# MotionDetector.net
KiCad netlist of a schematic drawn in Altium Designer
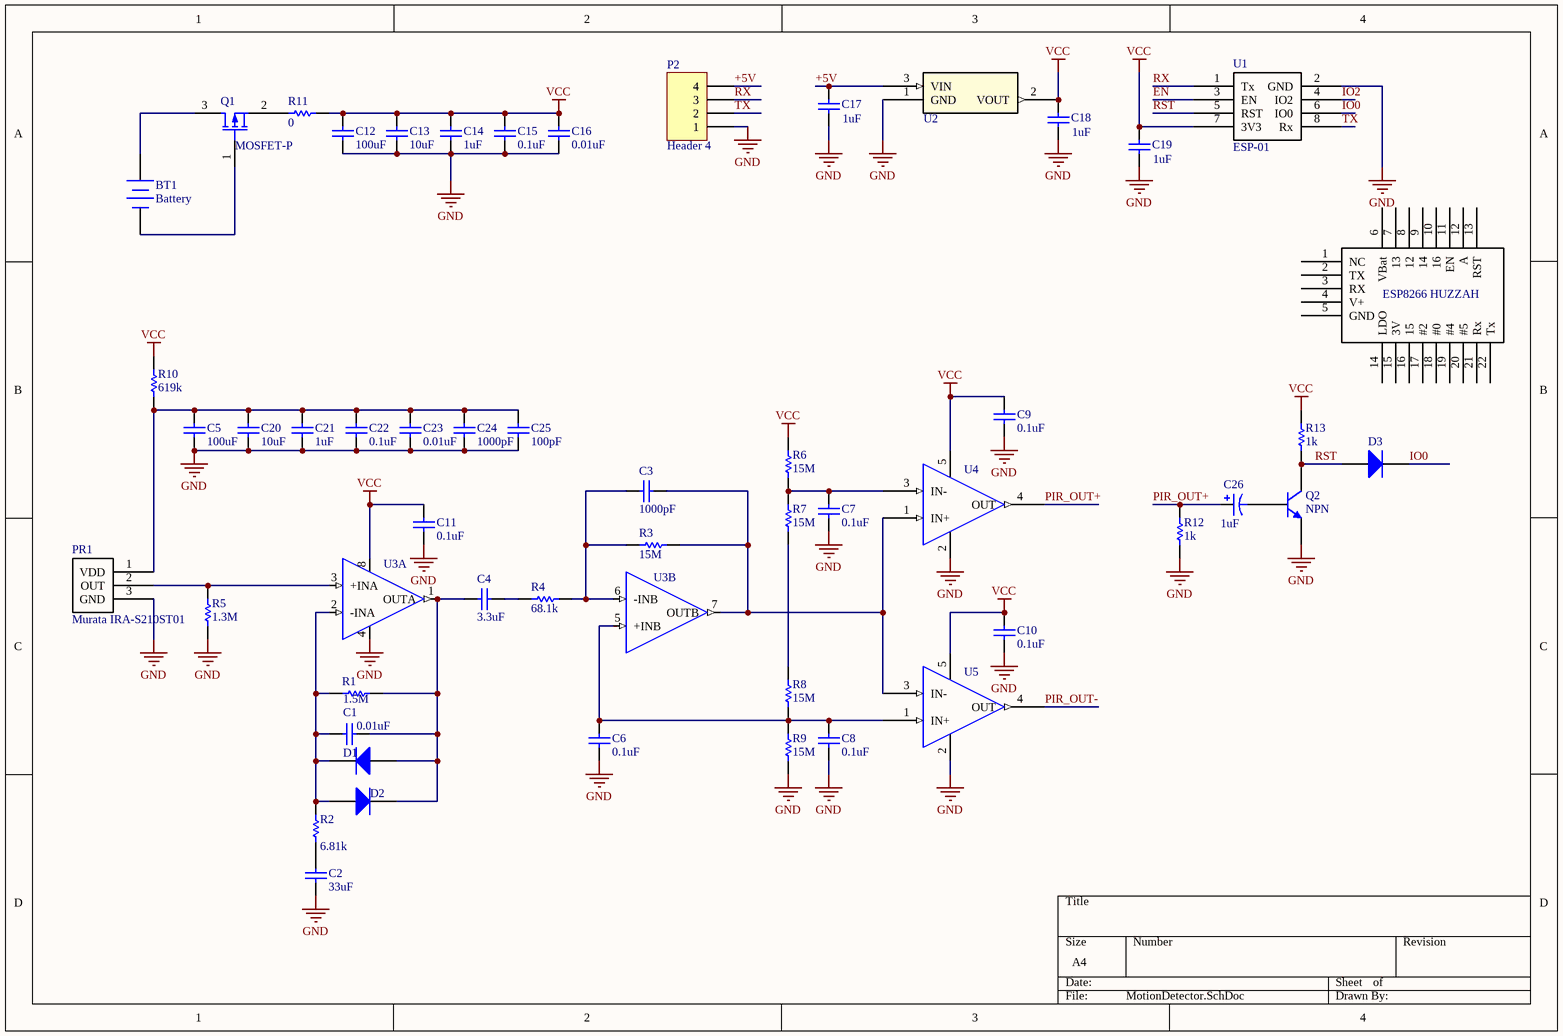
[diagram p0: MotionDetector.SchDoc]

(export (version "E")
  (design (tool "Eeschema 10.0.6"))
  (components
    (comp (ref "BT1")
      (value "Battery")
      (footprint "BAT-2")
      (description "Multicell Battery")
      (fields (field (name "PUBLISHER") "Altium Limited"))
      (libsource (lib "Miscellaneous Devices") (part "Battery"))
    )
    (comp (ref "C1")
      (value "0.01uF")
      (footprint "CAP_0804")
      (description "Capacitor")
      (fields (field (name "Comment") "Cap") (field (name "PUBLISHER") "Altium Limited"))
      (libsource (lib "Miscellaneous Devices") (part "Cap"))
    )
    (comp (ref "C2")
      (value "33uF")
      (footprint "CAP_0804")
      (description "Capacitor")
      (fields (field (name "Comment") "Cap") (field (name "PUBLISHER") "Altium Limited"))
      (libsource (lib "Miscellaneous Devices") (part "Cap"))
    )
    (comp (ref "C3")
      (value "1000pF")
      (footprint "CAP_0804")
      (description "Capacitor")
      (fields (field (name "Comment") "Cap") (field (name "PUBLISHER") "Altium Limited"))
      (libsource (lib "Miscellaneous Devices") (part "Cap"))
    )
    (comp (ref "C4")
      (value "3.3uF")
      (footprint "CAP_0804")
      (description "Capacitor")
      (fields (field (name "Comment") "Cap") (field (name "PUBLISHER") "Altium Limited"))
      (libsource (lib "Miscellaneous Devices") (part "Cap"))
    )
    (comp (ref "C5")
      (value "100uF")
      (footprint "CAP_0804")
      (description "Capacitor")
      (fields (field (name "Comment") "Cap") (field (name "PUBLISHER") "Altium Limited"))
      (libsource (lib "Miscellaneous Devices") (part "Cap"))
    )
    (comp (ref "C6")
      (value "0.1uF")
      (footprint "CAP_0804")
      (description "Capacitor")
      (fields (field (name "Comment") "Cap") (field (name "PUBLISHER") "Altium Limited"))
      (libsource (lib "Miscellaneous Devices") (part "Cap"))
    )
    (comp (ref "C7")
      (value "0.1uF")
      (footprint "CAP_0804")
      (description "Capacitor")
      (fields (field (name "Comment") "Cap") (field (name "PUBLISHER") "Altium Limited"))
      (libsource (lib "Miscellaneous Devices") (part "Cap"))
    )
    (comp (ref "C8")
      (value "0.1uF")
      (footprint "CAP_0804")
      (description "Capacitor")
      (fields (field (name "Comment") "Cap") (field (name "PUBLISHER") "Altium Limited"))
      (libsource (lib "Miscellaneous Devices") (part "Cap"))
    )
    (comp (ref "C9")
      (value "0.1uF")
      (footprint "CAP_0804")
      (description "Capacitor")
      (fields (field (name "Comment") "Cap") (field (name "PUBLISHER") "Altium Limited"))
      (libsource (lib "Miscellaneous Devices") (part "Cap"))
    )
    (comp (ref "C10")
      (value "0.1uF")
      (footprint "CAP_0804")
      (description "Capacitor")
      (fields (field (name "Comment") "Cap") (field (name "PUBLISHER") "Altium Limited"))
      (libsource (lib "Miscellaneous Devices") (part "Cap"))
    )
    (comp (ref "C11")
      (value "0.1uF")
      (footprint "CAP_0804")
      (description "Capacitor")
      (fields (field (name "Comment") "Cap") (field (name "PUBLISHER") "Altium Limited"))
      (libsource (lib "Miscellaneous Devices") (part "Cap"))
    )
    (comp (ref "C12")
      (value "100uF")
      (footprint "CAP_0804")
      (description "Capacitor")
      (fields (field (name "Comment") "Cap") (field (name "PUBLISHER") "Altium Limited"))
      (libsource (lib "Miscellaneous Devices") (part "Cap"))
    )
    (comp (ref "C13")
      (value "10uF")
      (footprint "CAP_0804")
      (description "Capacitor")
      (fields (field (name "Comment") "Cap") (field (name "PUBLISHER") "Altium Limited"))
      (libsource (lib "Miscellaneous Devices") (part "Cap"))
    )
    (comp (ref "C14")
      (value "1uF")
      (footprint "CAP_0804")
      (description "Capacitor")
      (fields (field (name "Comment") "Cap") (field (name "PUBLISHER") "Altium Limited"))
      (libsource (lib "Miscellaneous Devices") (part "Cap"))
    )
    (comp (ref "C15")
      (value "0.1uF")
      (footprint "CAP_0804")
      (description "Capacitor")
      (fields (field (name "Comment") "Cap") (field (name "PUBLISHER") "Altium Limited"))
      (libsource (lib "Miscellaneous Devices") (part "Cap"))
    )
    (comp (ref "C16")
      (value "0.01uF")
      (footprint "CAP_0804")
      (description "Capacitor")
      (fields (field (name "Comment") "Cap") (field (name "PUBLISHER") "Altium Limited"))
      (libsource (lib "Miscellaneous Devices") (part "Cap"))
    )
    (comp (ref "C17")
      (value "1uF")
      (footprint "CAP_0804")
      (description "Capacitor")
      (fields (field (name "Comment") "Cap") (field (name "PUBLISHER") "Altium Limited"))
      (libsource (lib "Miscellaneous Devices") (part "Cap"))
    )
    (comp (ref "C18")
      (value "1uF")
      (footprint "CAP_0804")
      (description "Capacitor")
      (fields (field (name "Comment") "Cap") (field (name "PUBLISHER") "Altium Limited"))
      (libsource (lib "Miscellaneous Devices") (part "Cap"))
    )
    (comp (ref "C19")
      (value "1uF")
      (footprint "CAP_0804")
      (description "Capacitor")
      (fields (field (name "Comment") "Cap") (field (name "PUBLISHER") "Altium Limited"))
      (libsource (lib "Miscellaneous Devices") (part "Cap"))
    )
    (comp (ref "C20")
      (value "10uF")
      (footprint "CAP_0804")
      (description "Capacitor")
      (fields (field (name "Comment") "Cap") (field (name "PUBLISHER") "Altium Limited"))
      (libsource (lib "Miscellaneous Devices") (part "Cap"))
    )
    (comp (ref "C21")
      (value "1uF")
      (footprint "CAP_0804")
      (description "Capacitor")
      (fields (field (name "Comment") "Cap") (field (name "PUBLISHER") "Altium Limited"))
      (libsource (lib "Miscellaneous Devices") (part "Cap"))
    )
    (comp (ref "C22")
      (value "0.1uF")
      (footprint "CAP_0804")
      (description "Capacitor")
      (fields (field (name "Comment") "Cap") (field (name "PUBLISHER") "Altium Limited"))
      (libsource (lib "Miscellaneous Devices") (part "Cap"))
    )
    (comp (ref "C23")
      (value "0.01uF")
      (footprint "CAP_0804")
      (description "Capacitor")
      (fields (field (name "Comment") "Cap") (field (name "PUBLISHER") "Altium Limited"))
      (libsource (lib "Miscellaneous Devices") (part "Cap"))
    )
    (comp (ref "C24")
      (value "1000pF")
      (footprint "CAP_0804")
      (description "Capacitor")
      (fields (field (name "Comment") "Cap") (field (name "PUBLISHER") "Altium Limited"))
      (libsource (lib "Miscellaneous Devices") (part "Cap"))
    )
    (comp (ref "C25")
      (value "100pF")
      (footprint "CAP_0804")
      (description "Capacitor")
      (fields (field (name "Comment") "Cap") (field (name "PUBLISHER") "Altium Limited"))
      (libsource (lib "Miscellaneous Devices") (part "Cap"))
    )
    (comp (ref "C26")
      (value "1uF")
      (footprint "RB7.6-15")
      (description "Polarized Capacitor (Radial)")
      (fields (field (name "Comment") "Cap Pol1") (field (name "PUBLISHER") "Altium Limited"))
      (libsource (lib "Miscellaneous Devices") (part "Cap Pol1"))
    )
    (comp (ref "D1")
      (value "Diode")
      (footprint "Diode SOD123")
      (description "Default Diode")
      (fields (field (name "PUBLISHER") "Altium Limited"))
      (libsource (lib "Miscellaneous Devices") (part "Diode"))
    )
    (comp (ref "D2")
      (value "Diode")
      (footprint "Diode SOD123")
      (description "Default Diode")
      (fields (field (name "PUBLISHER") "Altium Limited"))
      (libsource (lib "Miscellaneous Devices") (part "Diode"))
    )
    (comp (ref "D3")
      (value "Diode")
      (footprint "Diode SOD123")
      (description "Default Diode")
      (fields (field (name "PUBLISHER") "Altium Limited"))
      (libsource (lib "Miscellaneous Devices") (part "Diode"))
    )
    (comp (ref "ESP8266 HUZZAH")
      (value "Wifi module")
      (footprint "ESP8266 HUZZAH - duplicate")
      (description "U3")
      (libsource (lib "MotionDetectorSchematicLib") (part "U1"))
    )
    (comp (ref "P2")
      (value "Header 4")
      (footprint "HDR1X4")
      (description "Header, 4-Pin")
      (fields (field (name "PUBLISHER") "Altium Limited"))
      (libsource (lib "Miscellaneous Connectors") (part "Header 4"))
    )
    (comp (ref "PR1")
      (value "Murata IRA-S210ST01")
      (footprint "Murata IRA-S210ST01")
      (libsource (lib "MotionDetectorSchematicLib") (part "Murata IRA-S210ST01"))
    )
    (comp (ref "Q1")
      (value "MOSFET-P")
      (footprint "TO-236")
      (description "P-Channel MOSFET")
      (fields (field (name "PUBLISHER") "Altium Limited"))
      (libsource (lib "Miscellaneous Devices") (part "MOSFET-P"))
    )
    (comp (ref "Q2")
      (value "NPN")
      (footprint "TO-226-AA")
      (description "NPN Bipolar Transistor")
      (fields (field (name "PUBLISHER") "Altium Limited"))
      (libsource (lib "Miscellaneous Devices") (part "NPN"))
    )
    (comp (ref "R1")
      (value "1.5M")
      (footprint "RES_0804_panasonic")
      (description "Resistor")
      (fields (field (name "Comment") "Res1") (field (name "PUBLISHER") "Altium Limited"))
      (libsource (lib "Miscellaneous Devices") (part "Res1"))
    )
    (comp (ref "R2")
      (value "6.81k")
      (footprint "RES_0804_panasonic")
      (description "Resistor")
      (fields (field (name "Comment") "Res1") (field (name "PUBLISHER") "Altium Limited"))
      (libsource (lib "Miscellaneous Devices") (part "Res1"))
    )
    (comp (ref "R3")
      (value "15M")
      (footprint "RES_0804_panasonic")
      (description "Resistor")
      (fields (field (name "Comment") "Res1") (field (name "PUBLISHER") "Altium Limited"))
      (libsource (lib "Miscellaneous Devices") (part "Res1"))
    )
    (comp (ref "R4")
      (value "68.1k")
      (footprint "RES_0804_panasonic")
      (description "Resistor")
      (fields (field (name "Comment") "Res1") (field (name "PUBLISHER") "Altium Limited"))
      (libsource (lib "Miscellaneous Devices") (part "Res1"))
    )
    (comp (ref "R5")
      (value "1.3M")
      (footprint "RES_0804_panasonic")
      (description "Resistor")
      (fields (field (name "Comment") "Res1") (field (name "PUBLISHER") "Altium Limited"))
      (libsource (lib "Miscellaneous Devices") (part "Res1"))
    )
    (comp (ref "R6")
      (value "15M")
      (footprint "RES_0804_panasonic")
      (description "Resistor")
      (fields (field (name "Comment") "Res1") (field (name "PUBLISHER") "Altium Limited"))
      (libsource (lib "Miscellaneous Devices") (part "Res1"))
    )
    (comp (ref "R7")
      (value "15M")
      (footprint "RES_0804_panasonic")
      (description "Resistor")
      (fields (field (name "Comment") "Res1") (field (name "PUBLISHER") "Altium Limited"))
      (libsource (lib "Miscellaneous Devices") (part "Res1"))
    )
    (comp (ref "R8")
      (value "15M")
      (footprint "RES_0804_panasonic")
      (description "Resistor")
      (fields (field (name "Comment") "Res1") (field (name "PUBLISHER") "Altium Limited"))
      (libsource (lib "Miscellaneous Devices") (part "Res1"))
    )
    (comp (ref "R9")
      (value "15M")
      (footprint "RES_0804_panasonic")
      (description "Resistor")
      (fields (field (name "Comment") "Res1") (field (name "PUBLISHER") "Altium Limited"))
      (libsource (lib "Miscellaneous Devices") (part "Res1"))
    )
    (comp (ref "R10")
      (value "619k")
      (footprint "RES_0804_panasonic")
      (description "Resistor")
      (fields (field (name "Comment") "Res1") (field (name "PUBLISHER") "Altium Limited"))
      (libsource (lib "Miscellaneous Devices") (part "Res1"))
    )
    (comp (ref "R11")
      (value "0")
      (footprint "RES_0804_panasonic")
      (description "Resistor")
      (fields (field (name "Comment") "Res1") (field (name "PUBLISHER") "Altium Limited"))
      (libsource (lib "Miscellaneous Devices") (part "Res1"))
    )
    (comp (ref "R12")
      (value "1k")
      (footprint "RES_0804_panasonic")
      (description "Resistor")
      (fields (field (name "Comment") "Res1") (field (name "PUBLISHER") "Altium Limited"))
      (libsource (lib "Miscellaneous Devices") (part "Res1"))
    )
    (comp (ref "R13")
      (value "1k")
      (footprint "RES_0804_panasonic")
      (description "Resistor")
      (fields (field (name "Comment") "Res1") (field (name "PUBLISHER") "Altium Limited"))
      (libsource (lib "Miscellaneous Devices") (part "Res1"))
    )
    (comp (ref "U1")
      (value "ESP-01")
      (footprint "ESP-01")
      (libsource (lib "MotionDetectorSchematicLib") (part "ESP-01"))
    )
    (comp (ref "U2")
      (value "Voltage Reg")
      (footprint "SOT-23")
      (fields (field (name "MANUFACTURER_PART_NUMBER") "AP2120N-3.3TRG1"))
      (libsource (lib "MotionDetectorSchematicLib") (part "AP2120N-3.3TRG1"))
    )
    (comp (ref "U3")
      (value "LPV802DGKR")
      (footprint "SOP65P490X110-8N")
      (description "Dual Channel 320nA Nanopower Operational Amplifier 8-VSSOP -40 to 125")
      (fields (field (name "MF") "Texas Instruments") (field (name "DIGI-KEY_PART_NUMBER") "296-47341-1-ND"))
      (libsource (lib "MotionDetectorSchematicLib") (part "LPV802DGKR"))
    )
    (comp (ref "U4")
      (value "TLV3691IDCKR")
      (footprint "DCK5-M")
      (description "Comparator")
      (libsource (lib "MotionDetectorSchematicLib") (part "TLV3691IDCKR"))
    )
    (comp (ref "U5")
      (value "TLV3691IDCKR")
      (footprint "DCK5-M")
      (description "Comparator")
      (libsource (lib "MotionDetectorSchematicLib") (part "TLV3691IDCKR"))
    )
  )
  (nets
    (net (code "1") (name "/+5V") (class "Default")
      (node (ref "C17") (pin "2") (pinfunction "2_2") (pintype "passive"))
      (node (ref "P2") (pin "4") (pinfunction "4_4") (pintype "passive"))
      (node (ref "U2") (pin "3") (pinfunction "VIN_3") (pintype "input"))
    )
    (net (code "2") (name "/EN") (class "Default")
      (node (ref "U1") (pin "3") (pinfunction "EN_3") (pintype "passive"))
    )
    (net (code "3") (name "/IO0") (class "Default")
      (node (ref "D3") (pin "2") (pinfunction "K_2") (pintype "passive"))
      (node (ref "U1") (pin "6") (pinfunction "IO0_6") (pintype "passive"))
    )
    (net (code "4") (name "/IO2") (class "Default")
      (node (ref "U1") (pin "4") (pinfunction "IO2_4") (pintype "passive"))
    )
    (net (code "5") (name "/PIR_OUT+") (class "Default")
      (node (ref "C26") (pin "1") (pinfunction "1_1") (pintype "passive"))
      (node (ref "R12") (pin "1") (pinfunction "1_1") (pintype "passive"))
      (node (ref "U4") (pin "4") (pinfunction "OUT_4") (pintype "output"))
    )
    (net (code "6") (name "/PIR_OUT-") (class "Default")
      (node (ref "U5") (pin "4") (pinfunction "OUT_4") (pintype "output"))
    )
    (net (code "7") (name "/RST") (class "Default")
      (node (ref "D3") (pin "1") (pinfunction "A_1") (pintype "passive"))
      (node (ref "Q2") (pin "1") (pinfunction "C_1") (pintype "passive"))
      (node (ref "R13") (pin "2") (pinfunction "2_2") (pintype "passive"))
      (node (ref "U1") (pin "5") (pinfunction "RST_5") (pintype "passive"))
    )
    (net (code "8") (name "/RX") (class "Default")
      (node (ref "P2") (pin "3") (pinfunction "3_3") (pintype "passive"))
      (node (ref "U1") (pin "1") (pinfunction "Tx_1") (pintype "passive"))
    )
    (net (code "9") (name "/TX") (class "Default")
      (node (ref "P2") (pin "2") (pinfunction "2_2") (pintype "passive"))
      (node (ref "U1") (pin "8") (pinfunction "Rx_8") (pintype "passive"))
    )
    (net (code "10") (name "GND") (class "Default")
      (node (ref "C10") (pin "1") (pinfunction "1_1") (pintype "passive"))
      (node (ref "C11") (pin "1") (pinfunction "1_1") (pintype "passive"))
      (node (ref "C12") (pin "2") (pinfunction "2_2") (pintype "passive"))
      (node (ref "C13") (pin "2") (pinfunction "2_2") (pintype "passive"))
      (node (ref "C14") (pin "2") (pinfunction "2_2") (pintype "passive"))
      (node (ref "C15") (pin "2") (pinfunction "2_2") (pintype "passive"))
      (node (ref "C16") (pin "2") (pinfunction "2_2") (pintype "passive"))
      (node (ref "C17") (pin "1") (pinfunction "1_1") (pintype "passive"))
      (node (ref "C18") (pin "1") (pinfunction "1_1") (pintype "passive"))
      (node (ref "C19") (pin "1") (pinfunction "1_1") (pintype "passive"))
      (node (ref "C2") (pin "1") (pinfunction "1_1") (pintype "passive"))
      (node (ref "C20") (pin "2") (pinfunction "2_2") (pintype "passive"))
      (node (ref "C21") (pin "2") (pinfunction "2_2") (pintype "passive"))
      (node (ref "C22") (pin "2") (pinfunction "2_2") (pintype "passive"))
      (node (ref "C23") (pin "2") (pinfunction "2_2") (pintype "passive"))
      (node (ref "C24") (pin "2") (pinfunction "2_2") (pintype "passive"))
      (node (ref "C25") (pin "2") (pinfunction "2_2") (pintype "passive"))
      (node (ref "C5") (pin "2") (pinfunction "2_2") (pintype "passive"))
      (node (ref "C6") (pin "1") (pinfunction "1_1") (pintype "passive"))
      (node (ref "C7") (pin "1") (pinfunction "1_1") (pintype "passive"))
      (node (ref "C8") (pin "1") (pinfunction "1_1") (pintype "passive"))
      (node (ref "C9") (pin "1") (pinfunction "1_1") (pintype "passive"))
      (node (ref "P2") (pin "1") (pinfunction "1_1") (pintype "passive"))
      (node (ref "PR1") (pin "3") (pinfunction "GND_3") (pintype "passive"))
      (node (ref "Q2") (pin "3") (pinfunction "E_3") (pintype "passive"))
      (node (ref "R12") (pin "2") (pinfunction "2_2") (pintype "passive"))
      (node (ref "R5") (pin "2") (pinfunction "2_2") (pintype "passive"))
      (node (ref "R9") (pin "2") (pinfunction "2_2") (pintype "passive"))
      (node (ref "U1") (pin "2") (pinfunction "GND_2") (pintype "passive"))
      (node (ref "U2") (pin "1") (pinfunction "GND_1") (pintype "power_in"))
      (node (ref "U3") (pin "4") (pinfunction "V-_4") (pintype "power_in"))
      (node (ref "U4") (pin "2") (pinfunction "GND_2") (pintype "power_in"))
      (node (ref "U5") (pin "2") (pinfunction "GND_2") (pintype "power_in"))
    )
    (net (code "11") (name "Net-(BT1-+)") (class "Default")
      (node (ref "BT1") (pin "1") (pinfunction "+_1") (pintype "passive"))
      (node (ref "Q1") (pin "3") (pinfunction "D_3") (pintype "passive"))
    )
    (net (code "12") (name "Net-(BT1--)") (class "Default")
      (node (ref "BT1") (pin "2") (pinfunction "-_2") (pintype "passive"))
      (node (ref "Q1") (pin "1") (pinfunction "G_1") (pintype "passive"))
    )
    (net (code "13") (name "Net-(C2-Pad2)") (class "Default")
      (node (ref "C2") (pin "2") (pinfunction "2_2") (pintype "passive"))
      (node (ref "R2") (pin "1") (pinfunction "1_1") (pintype "passive"))
    )
    (net (code "14") (name "Net-(C4-Pad1)") (class "Default")
      (node (ref "C4") (pin "1") (pinfunction "1_1") (pintype "passive"))
      (node (ref "R4") (pin "2") (pinfunction "2_2") (pintype "passive"))
    )
    (net (code "15") (name "Net-(D1-A)") (class "Default")
      (node (ref "C1") (pin "2") (pinfunction "2_2") (pintype "passive"))
      (node (ref "C4") (pin "2") (pinfunction "2_2") (pintype "passive"))
      (node (ref "D1") (pin "1") (pinfunction "A_1") (pintype "passive"))
      (node (ref "D2") (pin "2") (pinfunction "K_2") (pintype "passive"))
      (node (ref "R1") (pin "2") (pinfunction "2_2") (pintype "passive"))
      (node (ref "U3") (pin "1") (pinfunction "OUTA_1") (pintype "output"))
    )
    (net (code "16") (name "Net-(D1-K)") (class "Default")
      (node (ref "C1") (pin "1") (pinfunction "1_1") (pintype "passive"))
      (node (ref "D1") (pin "2") (pinfunction "K_2") (pintype "passive"))
      (node (ref "D2") (pin "1") (pinfunction "A_1") (pintype "passive"))
      (node (ref "R1") (pin "1") (pinfunction "1_1") (pintype "passive"))
      (node (ref "R2") (pin "2") (pinfunction "2_2") (pintype "passive"))
      (node (ref "U3") (pin "2") (pinfunction "-INA_2") (pintype "input"))
    )
    (net (code "17") (name "Net-(PR1-OUT)") (class "Default")
      (node (ref "PR1") (pin "2") (pinfunction "OUT_2") (pintype "passive"))
      (node (ref "R5") (pin "1") (pinfunction "1_1") (pintype "passive"))
      (node (ref "U3") (pin "3") (pinfunction "+INA_3") (pintype "input"))
    )
    (net (code "18") (name "Net-(PR1-VDD)") (class "Default")
      (node (ref "C20") (pin "1") (pinfunction "1_1") (pintype "passive"))
      (node (ref "C21") (pin "1") (pinfunction "1_1") (pintype "passive"))
      (node (ref "C22") (pin "1") (pinfunction "1_1") (pintype "passive"))
      (node (ref "C23") (pin "1") (pinfunction "1_1") (pintype "passive"))
      (node (ref "C24") (pin "1") (pinfunction "1_1") (pintype "passive"))
      (node (ref "C25") (pin "1") (pinfunction "1_1") (pintype "passive"))
      (node (ref "C5") (pin "1") (pinfunction "1_1") (pintype "passive"))
      (node (ref "PR1") (pin "1") (pinfunction "VDD_1") (pintype "passive"))
      (node (ref "R10") (pin "2") (pinfunction "2_2") (pintype "passive"))
    )
    (net (code "19") (name "Net-(Q1-S)") (class "Default")
      (node (ref "Q1") (pin "2") (pinfunction "S_2") (pintype "passive"))
      (node (ref "R11") (pin "2") (pinfunction "2_2") (pintype "passive"))
    )
    (net (code "20") (name "Net-(Q2-B)") (class "Default")
      (node (ref "C26") (pin "2") (pinfunction "2_2") (pintype "passive"))
      (node (ref "Q2") (pin "2") (pinfunction "B_2") (pintype "passive"))
    )
    (net (code "21") (name "Net-(R7-Pad2)") (class "Default")
      (node (ref "R7") (pin "2") (pinfunction "2_2") (pintype "passive"))
      (node (ref "R8") (pin "1") (pinfunction "1_1") (pintype "passive"))
    )
    (net (code "22") (name "Net-(U3B-+INB)") (class "Default")
      (node (ref "C6") (pin "2") (pinfunction "2_2") (pintype "passive"))
      (node (ref "C8") (pin "2") (pinfunction "2_2") (pintype "passive"))
      (node (ref "R8") (pin "2") (pinfunction "2_2") (pintype "passive"))
      (node (ref "R9") (pin "1") (pinfunction "1_1") (pintype "passive"))
      (node (ref "U3") (pin "5") (pinfunction "+INB_5") (pintype "input"))
      (node (ref "U5") (pin "1") (pinfunction "IN+_1") (pintype "input"))
    )
    (net (code "23") (name "Net-(U3B--INB)") (class "Default")
      (node (ref "C3") (pin "2") (pinfunction "2_2") (pintype "passive"))
      (node (ref "R3") (pin "2") (pinfunction "2_2") (pintype "passive"))
      (node (ref "R4") (pin "1") (pinfunction "1_1") (pintype "passive"))
      (node (ref "U3") (pin "6") (pinfunction "-INB_6") (pintype "input"))
    )
    (net (code "24") (name "Net-(U3B-OUTB)") (class "Default")
      (node (ref "C3") (pin "1") (pinfunction "1_1") (pintype "passive"))
      (node (ref "R3") (pin "1") (pinfunction "1_1") (pintype "passive"))
      (node (ref "U3") (pin "7") (pinfunction "OUTB_7") (pintype "output"))
      (node (ref "U4") (pin "1") (pinfunction "IN+_1") (pintype "input"))
      (node (ref "U5") (pin "3") (pinfunction "IN-_3") (pintype "input"))
    )
    (net (code "25") (name "Net-(U4-IN-)") (class "Default")
      (node (ref "C7") (pin "2") (pinfunction "2_2") (pintype "passive"))
      (node (ref "R6") (pin "2") (pinfunction "2_2") (pintype "passive"))
      (node (ref "R7") (pin "1") (pinfunction "1_1") (pintype "passive"))
      (node (ref "U4") (pin "3") (pinfunction "IN-_3") (pintype "input"))
    )
    (net (code "26") (name "VCC") (class "Default")
      (node (ref "C10") (pin "2") (pinfunction "2_2") (pintype "passive"))
      (node (ref "C11") (pin "2") (pinfunction "2_2") (pintype "passive"))
      (node (ref "C12") (pin "1") (pinfunction "1_1") (pintype "passive"))
      (node (ref "C13") (pin "1") (pinfunction "1_1") (pintype "passive"))
      (node (ref "C14") (pin "1") (pinfunction "1_1") (pintype "passive"))
      (node (ref "C15") (pin "1") (pinfunction "1_1") (pintype "passive"))
      (node (ref "C16") (pin "1") (pinfunction "1_1") (pintype "passive"))
      (node (ref "C18") (pin "2") (pinfunction "2_2") (pintype "passive"))
      (node (ref "C19") (pin "2") (pinfunction "2_2") (pintype "passive"))
      (node (ref "C9") (pin "2") (pinfunction "2_2") (pintype "passive"))
      (node (ref "R10") (pin "1") (pinfunction "1_1") (pintype "passive"))
      (node (ref "R11") (pin "1") (pinfunction "1_1") (pintype "passive"))
      (node (ref "R13") (pin "1") (pinfunction "1_1") (pintype "passive"))
      (node (ref "R6") (pin "1") (pinfunction "1_1") (pintype "passive"))
      (node (ref "U1") (pin "7") (pinfunction "3V3_7") (pintype "passive"))
      (node (ref "U2") (pin "2") (pinfunction "VOUT_2") (pintype "output"))
      (node (ref "U3") (pin "8") (pinfunction "V+_8") (pintype "power_in"))
      (node (ref "U4") (pin "5") (pinfunction "VCC_5") (pintype "power_in"))
      (node (ref "U5") (pin "5") (pinfunction "VCC_5") (pintype "power_in"))
    )
    (net (code "27") (name "unconnected-(ESP8266 HUZZAH-#0-Pad18)") (class "Default")
      (node (ref "ESP8266 HUZZAH") (pin "18") (pinfunction "#0_18") (pintype "passive"))
    )
    (net (code "28") (name "unconnected-(ESP8266 HUZZAH-#2-Pad17)") (class "Default")
      (node (ref "ESP8266 HUZZAH") (pin "17") (pinfunction "#2_17") (pintype "passive"))
    )
    (net (code "29") (name "unconnected-(ESP8266 HUZZAH-#4-Pad19)") (class "Default")
      (node (ref "ESP8266 HUZZAH") (pin "19") (pinfunction "#4_19") (pintype "passive"))
    )
    (net (code "30") (name "unconnected-(ESP8266 HUZZAH-#5-Pad20)") (class "Default")
      (node (ref "ESP8266 HUZZAH") (pin "20") (pinfunction "#5_20") (pintype "passive"))
    )
    (net (code "31") (name "unconnected-(ESP8266 HUZZAH-3V-Pad15)") (class "Default")
      (node (ref "ESP8266 HUZZAH") (pin "15") (pinfunction "3V_15") (pintype "passive"))
    )
    (net (code "32") (name "unconnected-(ESP8266 HUZZAH-12-Pad8)") (class "Default")
      (node (ref "ESP8266 HUZZAH") (pin "8") (pinfunction "12_8") (pintype "passive"))
    )
    (net (code "33") (name "unconnected-(ESP8266 HUZZAH-13-Pad7)") (class "Default")
      (node (ref "ESP8266 HUZZAH") (pin "7") (pinfunction "13_7") (pintype "passive"))
    )
    (net (code "34") (name "unconnected-(ESP8266 HUZZAH-14-Pad9)") (class "Default")
      (node (ref "ESP8266 HUZZAH") (pin "9") (pinfunction "14_9") (pintype "passive"))
    )
    (net (code "35") (name "unconnected-(ESP8266 HUZZAH-15-Pad16)") (class "Default")
      (node (ref "ESP8266 HUZZAH") (pin "16") (pinfunction "15_16") (pintype "passive"))
    )
    (net (code "36") (name "unconnected-(ESP8266 HUZZAH-16-Pad10)") (class "Default")
      (node (ref "ESP8266 HUZZAH") (pin "10") (pinfunction "16_10") (pintype "passive"))
    )
    (net (code "37") (name "unconnected-(ESP8266 HUZZAH-A-Pad12)") (class "Default")
      (node (ref "ESP8266 HUZZAH") (pin "12") (pinfunction "A_12") (pintype "passive"))
    )
    (net (code "38") (name "unconnected-(ESP8266 HUZZAH-EN-Pad11)") (class "Default")
      (node (ref "ESP8266 HUZZAH") (pin "11") (pinfunction "EN_11") (pintype "passive"))
    )
    (net (code "39") (name "unconnected-(ESP8266 HUZZAH-GND-Pad5)") (class "Default")
      (node (ref "ESP8266 HUZZAH") (pin "5") (pinfunction "GND_5") (pintype "passive"))
    )
    (net (code "40") (name "unconnected-(ESP8266 HUZZAH-LDO-Pad14)") (class "Default")
      (node (ref "ESP8266 HUZZAH") (pin "14") (pinfunction "LDO_14") (pintype "passive"))
    )
    (net (code "41") (name "unconnected-(ESP8266 HUZZAH-NC-Pad1)") (class "Default")
      (node (ref "ESP8266 HUZZAH") (pin "1") (pinfunction "NC_1") (pintype "passive"))
    )
    (net (code "42") (name "unconnected-(ESP8266 HUZZAH-RST-Pad13)") (class "Default")
      (node (ref "ESP8266 HUZZAH") (pin "13") (pinfunction "RST_13") (pintype "passive"))
    )
    (net (code "43") (name "unconnected-(ESP8266 HUZZAH-RX-Pad3)") (class "Default")
      (node (ref "ESP8266 HUZZAH") (pin "3") (pinfunction "RX_3") (pintype "passive"))
    )
    (net (code "44") (name "unconnected-(ESP8266 HUZZAH-Rx-Pad21)") (class "Default")
      (node (ref "ESP8266 HUZZAH") (pin "21") (pinfunction "Rx_21") (pintype "passive"))
    )
    (net (code "45") (name "unconnected-(ESP8266 HUZZAH-TX-Pad2)") (class "Default")
      (node (ref "ESP8266 HUZZAH") (pin "2") (pinfunction "TX_2") (pintype "passive"))
    )
    (net (code "46") (name "unconnected-(ESP8266 HUZZAH-Tx-Pad22)") (class "Default")
      (node (ref "ESP8266 HUZZAH") (pin "22") (pinfunction "Tx_22") (pintype "passive"))
    )
    (net (code "47") (name "unconnected-(ESP8266 HUZZAH-V+-Pad4)") (class "Default")
      (node (ref "ESP8266 HUZZAH") (pin "4") (pinfunction "V+_4") (pintype "passive"))
    )
    (net (code "48") (name "unconnected-(ESP8266 HUZZAH-VBat-Pad6)") (class "Default")
      (node (ref "ESP8266 HUZZAH") (pin "6") (pinfunction "VBat_6") (pintype "passive"))
    )
  )
)
